# diyduino.net
KiCad netlist of a schematic drawn in EAGLE
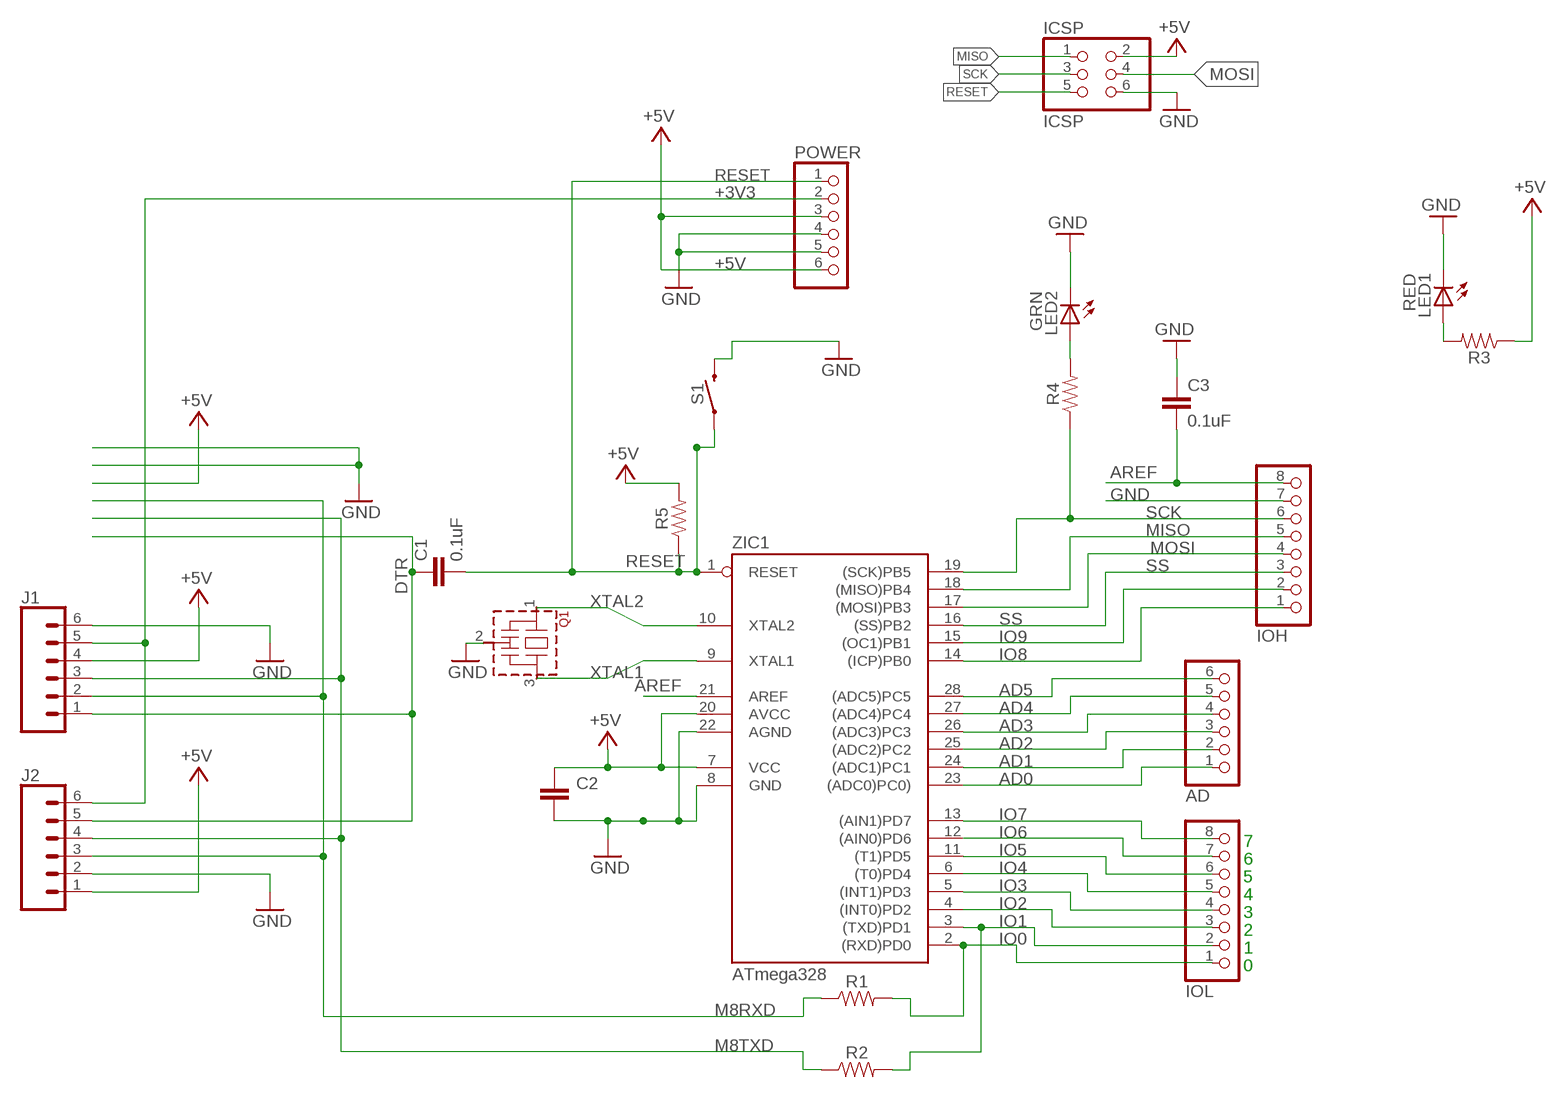
[diagram p0: schematic, sheet 1]

(export (version "E")
  (design (tool "Eeschema 10.0.6"))
  (components
    (comp (ref "AD")
      (value "PINHD-1X6")
      (footprint "eagle-import:1X06")
      (libsource (lib "eagle-import") (part "PINHD-1X6"))
    )
    (comp (ref "C1")
      (value "0.1uF")
      (footprint "eagle-import:C2.5-2")
      (libsource (lib "eagle-import") (part "C2.5/2"))
    )
    (comp (ref "C2")
      (value "0.1uF")
      (footprint "eagle-import:C2.5-2")
      (libsource (lib "eagle-import") (part "C2.5/2"))
    )
    (comp (ref "C3")
      (value "0.1uF")
      (footprint "eagle-import:C2.5-2")
      (libsource (lib "eagle-import") (part "C2.5/2"))
    )
    (comp (ref "ICSP")
      (value "ICSP")
      (footprint "eagle-import:2X03")
      (libsource (lib "eagle-import") (part "PINHD-2X3"))
    )
    (comp (ref "IOH")
      (value "PINHD-1X8")
      (footprint "eagle-import:1X08")
      (libsource (lib "eagle-import") (part "PINHD-1X8"))
    )
    (comp (ref "IOL")
      (value "PINHD-1X8")
      (footprint "eagle-import:1X08")
      (libsource (lib "eagle-import") (part "PINHD-1X8"))
    )
    (comp (ref "J1")
      (value "CONN_06SILK_FEMALE_PTH")
      (footprint "eagle-import:1X06")
      (libsource (lib "eagle-import") (part "CONN_06SILK_FEMALE_PTH"))
    )
    (comp (ref "J2")
      (value "CONN_06SILK_FEMALE_PTH")
      (footprint "eagle-import:1X06")
      (libsource (lib "eagle-import") (part "CONN_06SILK_FEMALE_PTH"))
    )
    (comp (ref "LED1")
      (value "RED")
      (footprint "eagle-import:LED3MM")
      (libsource (lib "eagle-import") (part "LED3MM"))
    )
    (comp (ref "LED2")
      (value "GRN")
      (footprint "eagle-import:LED3MM")
      (libsource (lib "eagle-import") (part "LED3MM"))
    )
    (comp (ref "POWER")
      (value "PINHD-1X6")
      (footprint "eagle-import:1X06")
      (libsource (lib "eagle-import") (part "PINHD-1X6"))
    )
    (comp (ref "Q1")
      (value "CSTLS_X")
      (footprint "eagle-import:CSTLS_X")
      (libsource (lib "eagle-import") (part "CSTLS_X"))
    )
    (comp (ref "R1")
      (value "RESISTORAXIAL-0.3")
      (footprint "eagle-import:AXIAL-0.3")
      (libsource (lib "eagle-import") (part "RESISTORAXIAL-0.3"))
    )
    (comp (ref "R2")
      (value "RESISTORAXIAL-0.3")
      (footprint "eagle-import:AXIAL-0.3")
      (libsource (lib "eagle-import") (part "RESISTORAXIAL-0.3"))
    )
    (comp (ref "R3")
      (value "RESISTORAXIAL-0.3")
      (footprint "eagle-import:AXIAL-0.3")
      (libsource (lib "eagle-import") (part "RESISTORAXIAL-0.3"))
    )
    (comp (ref "R4")
      (value "RESISTORAXIAL-0.3")
      (footprint "eagle-import:AXIAL-0.3")
      (libsource (lib "eagle-import") (part "RESISTORAXIAL-0.3"))
    )
    (comp (ref "R5")
      (value "RESISTORAXIAL-0.3")
      (footprint "eagle-import:AXIAL-0.3")
      (libsource (lib "eagle-import") (part "RESISTORAXIAL-0.3"))
    )
    (comp (ref "S1")
      (value "MOMENTARY-SWITCH-SPST-PTH-6.0MM")
      (footprint "eagle-import:TACTILE_SWITCH_PTH_6.0MM")
      (libsource (lib "eagle-import") (part "MOMENTARY-SWITCH-SPST-PTH-6.0MM"))
    )
    (comp (ref "ZIC1")
      (value "ATmega328")
      (footprint "eagle-import:DIL28-3")
      (libsource (lib "eagle-import") (part "AT90S4433P"))
    )
  )
  (nets
    (net (code "1") (name "+5V") (class "Default")
      (node (ref "C2") (pin "2") (pinfunction "2_2") (pintype "passive"))
      (node (ref "ICSP") (pin "2") (pinfunction "2_2") (pintype "passive"))
      (node (ref "J1") (pin "4") (pinfunction "4_4") (pintype "passive"))
      (node (ref "J2") (pin "1") (pinfunction "1_1") (pintype "passive"))
      (node (ref "POWER") (pin "3") (pinfunction "3_3") (pintype "passive"))
      (node (ref "POWER") (pin "6") (pinfunction "6_6") (pintype "passive"))
      (node (ref "R3") (pin "P$1") (pinfunction "1_P$1") (pintype "passive"))
      (node (ref "R5") (pin "P$2") (pinfunction "2_P$2") (pintype "passive"))
      (node (ref "ZIC1") (pin "20") (pinfunction "AVCC_20") (pintype "power_in"))
      (node (ref "ZIC1") (pin "7") (pinfunction "VCC_7") (pintype "power_in"))
    )
    (net (code "2") (name "/+3V3") (class "Default")
      (node (ref "J1") (pin "5") (pinfunction "5_5") (pintype "passive"))
      (node (ref "J2") (pin "6") (pinfunction "6_6") (pintype "passive"))
      (node (ref "POWER") (pin "2") (pinfunction "2_2") (pintype "passive"))
    )
    (net (code "3") (name "/AD0") (class "Default")
      (node (ref "AD") (pin "1") (pinfunction "1_1") (pintype "passive"))
      (node (ref "ZIC1") (pin "23") (pinfunction "(ADC0)PC0)_23") (pintype "bidirectional"))
    )
    (net (code "4") (name "/AD1") (class "Default")
      (node (ref "AD") (pin "2") (pinfunction "2_2") (pintype "passive"))
      (node (ref "ZIC1") (pin "24") (pinfunction "(ADC1)PC1_24") (pintype "bidirectional"))
    )
    (net (code "5") (name "/AD2") (class "Default")
      (node (ref "AD") (pin "3") (pinfunction "3_3") (pintype "passive"))
      (node (ref "ZIC1") (pin "25") (pinfunction "(ADC2)PC2_25") (pintype "bidirectional"))
    )
    (net (code "6") (name "/AD3") (class "Default")
      (node (ref "AD") (pin "4") (pinfunction "4_4") (pintype "passive"))
      (node (ref "ZIC1") (pin "26") (pinfunction "(ADC3)PC3_26") (pintype "bidirectional"))
    )
    (net (code "7") (name "/AD4") (class "Default")
      (node (ref "AD") (pin "5") (pinfunction "5_5") (pintype "passive"))
      (node (ref "ZIC1") (pin "27") (pinfunction "(ADC4)PC4_27") (pintype "bidirectional"))
    )
    (net (code "8") (name "/AD5") (class "Default")
      (node (ref "AD") (pin "6") (pinfunction "6_6") (pintype "passive"))
      (node (ref "ZIC1") (pin "28") (pinfunction "(ADC5)PC5_28") (pintype "bidirectional"))
    )
    (net (code "9") (name "/AREF") (class "Default")
      (node (ref "C3") (pin "2") (pinfunction "2_2") (pintype "passive"))
      (node (ref "IOH") (pin "8") (pinfunction "8_8") (pintype "passive"))
      (node (ref "ZIC1") (pin "21") (pinfunction "AREF_21") (pintype "passive"))
    )
    (net (code "10") (name "/DTR") (class "Default")
      (node (ref "C1") (pin "1") (pinfunction "1_1") (pintype "passive"))
      (node (ref "J1") (pin "1") (pinfunction "1_1") (pintype "passive"))
      (node (ref "J2") (pin "5") (pinfunction "5_5") (pintype "passive"))
    )
    (net (code "11") (name "/IO0") (class "Default")
      (node (ref "IOL") (pin "1") (pinfunction "1_1") (pintype "passive"))
      (node (ref "R1") (pin "P$2") (pinfunction "2_P$2") (pintype "passive"))
      (node (ref "ZIC1") (pin "2") (pinfunction "(RXD)PD0_2") (pintype "bidirectional"))
    )
    (net (code "12") (name "/IO1") (class "Default")
      (node (ref "IOL") (pin "2") (pinfunction "2_2") (pintype "passive"))
      (node (ref "R2") (pin "P$2") (pinfunction "2_P$2") (pintype "passive"))
      (node (ref "ZIC1") (pin "3") (pinfunction "(TXD)PD1_3") (pintype "bidirectional"))
    )
    (net (code "13") (name "/IO2") (class "Default")
      (node (ref "IOL") (pin "3") (pinfunction "3_3") (pintype "passive"))
      (node (ref "ZIC1") (pin "4") (pinfunction "(INT0)PD2_4") (pintype "bidirectional"))
    )
    (net (code "14") (name "/IO3") (class "Default")
      (node (ref "IOL") (pin "4") (pinfunction "4_4") (pintype "passive"))
      (node (ref "ZIC1") (pin "5") (pinfunction "(INT1)PD3_5") (pintype "bidirectional"))
    )
    (net (code "15") (name "/IO4") (class "Default")
      (node (ref "IOL") (pin "5") (pinfunction "5_5") (pintype "passive"))
      (node (ref "ZIC1") (pin "6") (pinfunction "(T0)PD4_6") (pintype "bidirectional"))
    )
    (net (code "16") (name "/IO5") (class "Default")
      (node (ref "IOL") (pin "6") (pinfunction "6_6") (pintype "passive"))
      (node (ref "ZIC1") (pin "11") (pinfunction "(T1)PD5_11") (pintype "bidirectional"))
    )
    (net (code "17") (name "/IO6") (class "Default")
      (node (ref "IOL") (pin "7") (pinfunction "7_7") (pintype "passive"))
      (node (ref "ZIC1") (pin "12") (pinfunction "(AIN0)PD6_12") (pintype "bidirectional"))
    )
    (net (code "18") (name "/IO7") (class "Default")
      (node (ref "IOL") (pin "8") (pinfunction "8_8") (pintype "passive"))
      (node (ref "ZIC1") (pin "13") (pinfunction "(AIN1)PD7_13") (pintype "bidirectional"))
    )
    (net (code "19") (name "/IO8") (class "Default")
      (node (ref "IOH") (pin "1") (pinfunction "1_1") (pintype "passive"))
      (node (ref "ZIC1") (pin "14") (pinfunction "(ICP)PB0_14") (pintype "bidirectional"))
    )
    (net (code "20") (name "/IO9") (class "Default")
      (node (ref "IOH") (pin "2") (pinfunction "2_2") (pintype "passive"))
      (node (ref "ZIC1") (pin "15") (pinfunction "(OC1)PB1_15") (pintype "bidirectional"))
    )
    (net (code "21") (name "/M8RXD") (class "Default")
      (node (ref "J1") (pin "2") (pinfunction "2_2") (pintype "passive"))
      (node (ref "J2") (pin "3") (pinfunction "3_3") (pintype "passive"))
      (node (ref "R1") (pin "P$1") (pinfunction "1_P$1") (pintype "passive"))
    )
    (net (code "22") (name "/M8TXD") (class "Default")
      (node (ref "J1") (pin "3") (pinfunction "3_3") (pintype "passive"))
      (node (ref "J2") (pin "4") (pinfunction "4_4") (pintype "passive"))
      (node (ref "R2") (pin "P$1") (pinfunction "1_P$1") (pintype "passive"))
    )
    (net (code "23") (name "/SS") (class "Default")
      (node (ref "IOH") (pin "3") (pinfunction "3_3") (pintype "passive"))
      (node (ref "ZIC1") (pin "16") (pinfunction "(SS)PB2_16") (pintype "bidirectional"))
    )
    (net (code "24") (name "/XTAL1") (class "Default")
      (node (ref "Q1") (pin "3") (pinfunction "3_3") (pintype "input"))
      (node (ref "ZIC1") (pin "9") (pinfunction "XTAL1_9") (pintype "bidirectional"))
    )
    (net (code "25") (name "/XTAL2") (class "Default")
      (node (ref "Q1") (pin "1") (pinfunction "1_1") (pintype "output"))
      (node (ref "ZIC1") (pin "10") (pinfunction "XTAL2_10") (pintype "bidirectional"))
    )
    (net (code "26") (name "GND") (class "Default")
      (node (ref "C2") (pin "1") (pinfunction "1_1") (pintype "passive"))
      (node (ref "C3") (pin "1") (pinfunction "1_1") (pintype "passive"))
      (node (ref "ICSP") (pin "6") (pinfunction "6_6") (pintype "passive"))
      (node (ref "IOH") (pin "7") (pinfunction "7_7") (pintype "passive"))
      (node (ref "J1") (pin "6") (pinfunction "6_6") (pintype "passive"))
      (node (ref "J2") (pin "2") (pinfunction "2_2") (pintype "passive"))
      (node (ref "LED1") (pin "K") (pinfunction "C_K") (pintype "passive"))
      (node (ref "LED2") (pin "K") (pinfunction "C_K") (pintype "passive"))
      (node (ref "POWER") (pin "4") (pinfunction "4_4") (pintype "passive"))
      (node (ref "POWER") (pin "5") (pinfunction "5_5") (pintype "passive"))
      (node (ref "Q1") (pin "2") (pinfunction "VSS_2") (pintype "power_in"))
      (node (ref "S1") (pin "3") (pinfunction "2_3") (pintype "passive"))
      (node (ref "ZIC1") (pin "22") (pinfunction "AGND_22") (pintype "power_in"))
      (node (ref "ZIC1") (pin "8") (pinfunction "GND_8") (pintype "power_in"))
    )
    (net (code "27") (name "MISO") (class "Default")
      (node (ref "ICSP") (pin "1") (pinfunction "1_1") (pintype "passive"))
      (node (ref "IOH") (pin "5") (pinfunction "5_5") (pintype "passive"))
      (node (ref "ZIC1") (pin "18") (pinfunction "(MISO)PB4_18") (pintype "bidirectional"))
    )
    (net (code "28") (name "MOSI") (class "Default")
      (node (ref "ICSP") (pin "4") (pinfunction "4_4") (pintype "passive"))
      (node (ref "IOH") (pin "4") (pinfunction "4_4") (pintype "passive"))
      (node (ref "ZIC1") (pin "17") (pinfunction "(MOSI)PB3_17") (pintype "bidirectional"))
    )
    (net (code "29") (name "Net-(R3-2)") (class "Default")
      (node (ref "LED1") (pin "A") (pinfunction "A_A") (pintype "passive"))
      (node (ref "R3") (pin "P$2") (pinfunction "2_P$2") (pintype "passive"))
    )
    (net (code "30") (name "Net-(R4-2)") (class "Default")
      (node (ref "LED2") (pin "A") (pinfunction "A_A") (pintype "passive"))
      (node (ref "R4") (pin "P$2") (pinfunction "2_P$2") (pintype "passive"))
    )
    (net (code "31") (name "RESET") (class "Default")
      (node (ref "C1") (pin "2") (pinfunction "2_2") (pintype "passive"))
      (node (ref "ICSP") (pin "5") (pinfunction "5_5") (pintype "passive"))
      (node (ref "POWER") (pin "1") (pinfunction "1_1") (pintype "passive"))
      (node (ref "R5") (pin "P$1") (pinfunction "1_P$1") (pintype "passive"))
      (node (ref "S1") (pin "1") (pinfunction "1_1") (pintype "passive"))
      (node (ref "ZIC1") (pin "1") (pinfunction "RESET_1") (pintype "input"))
    )
    (net (code "32") (name "SCK") (class "Default")
      (node (ref "ICSP") (pin "3") (pinfunction "3_3") (pintype "passive"))
      (node (ref "IOH") (pin "6") (pinfunction "6_6") (pintype "passive"))
      (node (ref "R4") (pin "P$1") (pinfunction "1_P$1") (pintype "passive"))
      (node (ref "ZIC1") (pin "19") (pinfunction "(SCK)PB5_19") (pintype "bidirectional"))
    )
  )
)
